# rapidshark-motor-filter-mk-1_0.net
KiCad netlist of a schematic drawn in EAGLE
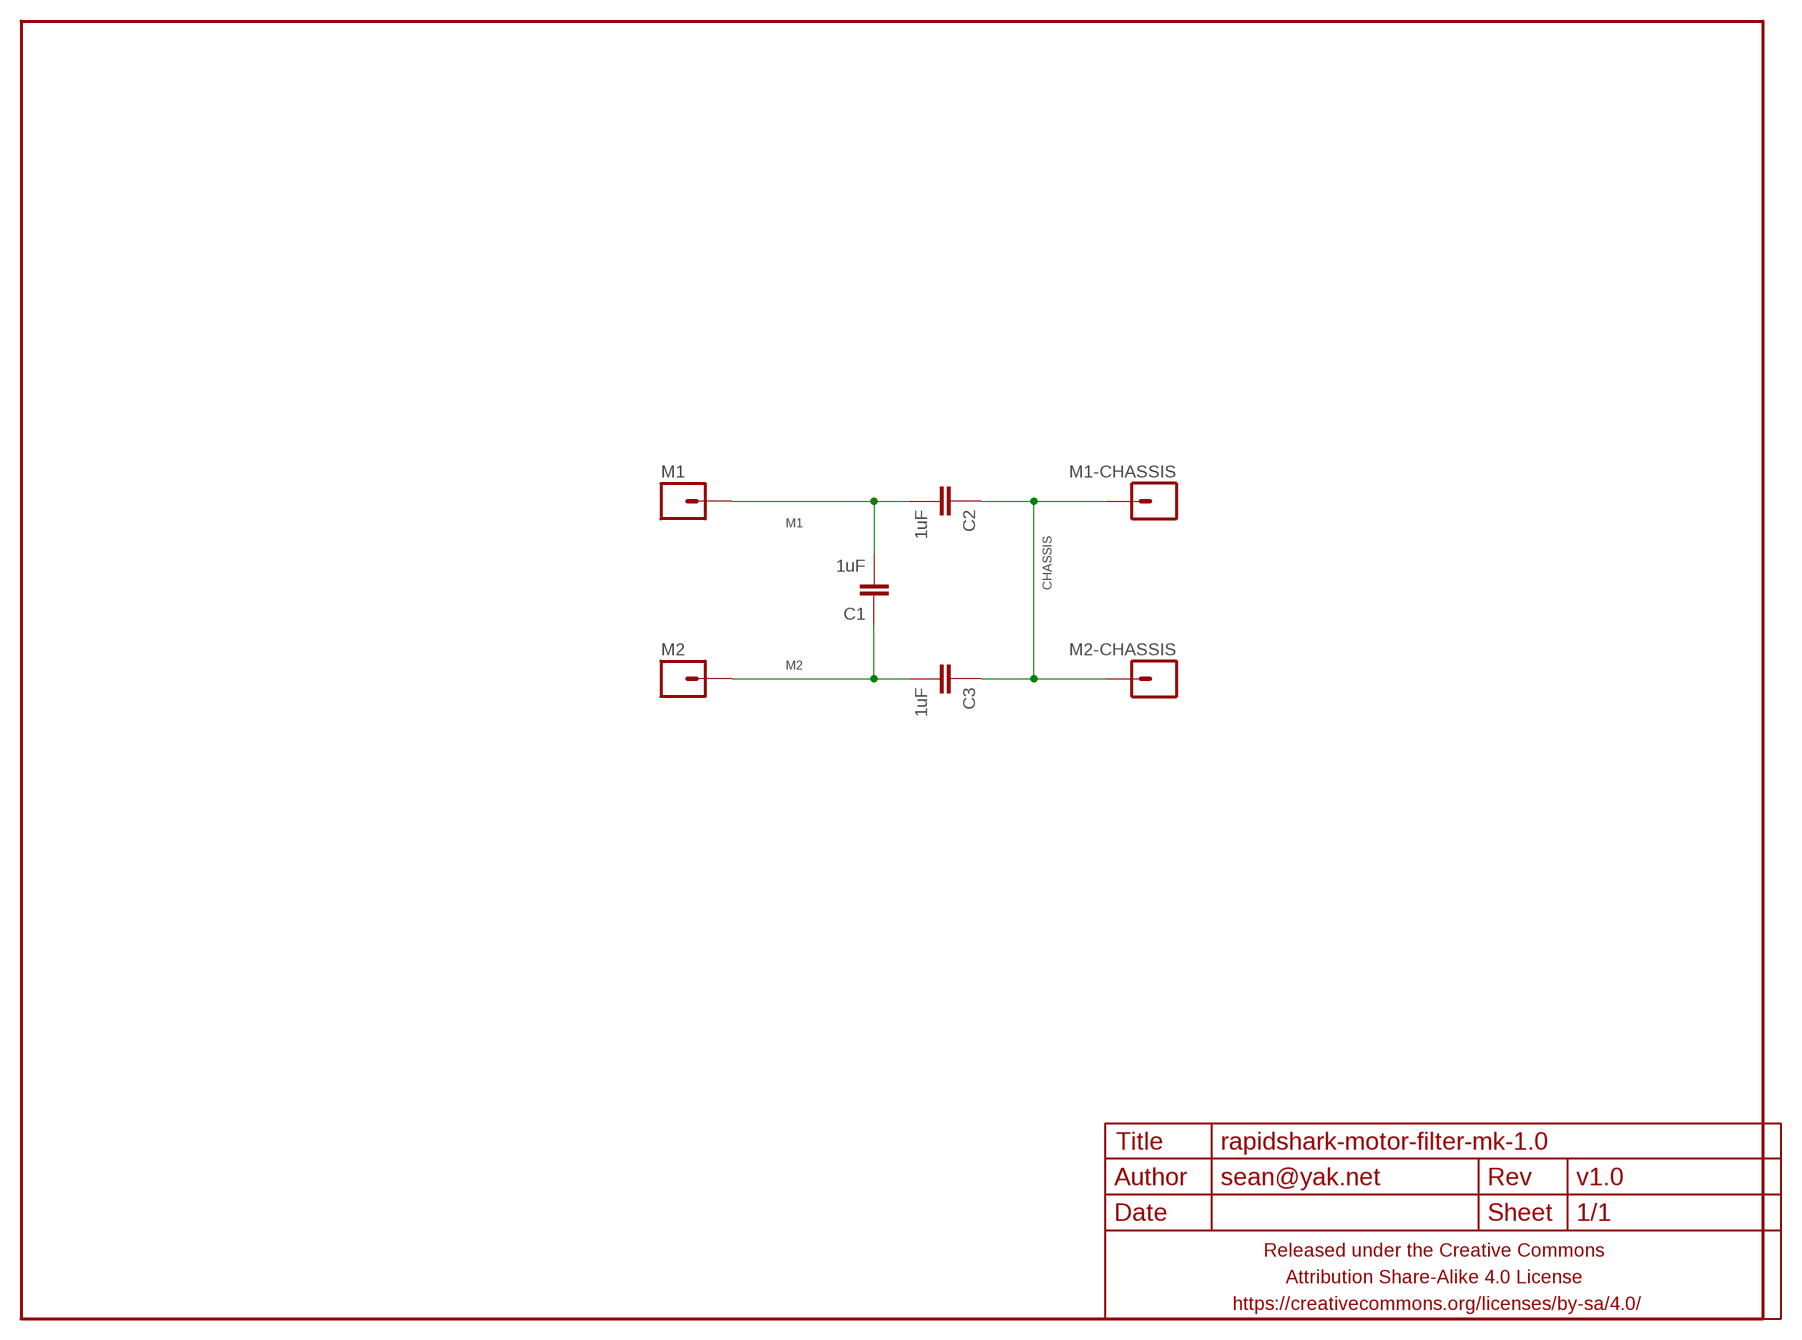
[diagram p0: schematic, sheet 1]

(export (version "E")
  (design (tool "Eeschema 10.0.6"))
  (components
    (comp (ref "C1")
      (value "1uF")
      (footprint "eagle-import:C0805-TIGHTER")
      (libsource (lib "eagle-import") (part "CAPACITOR-CERAMICC0805-TIGHTER"))
    )
    (comp (ref "C2")
      (value "1uF")
      (footprint "eagle-import:C0805-TIGHTER")
      (libsource (lib "eagle-import") (part "CAPACITOR-CERAMICC0805-TIGHTER"))
    )
    (comp (ref "C3")
      (value "1uF")
      (footprint "eagle-import:C0805-TIGHTER")
      (libsource (lib "eagle-import") (part "CAPACITOR-CERAMICC0805-TIGHTER"))
    )
    (comp (ref "FRAME1")
      (value "FRAME-LETTERNO_PACKAGE")
      (footprint "eagle-import:DUMMY")
      (fields (field (name "DESIGNER") "sean@yak.net") (field (name "VERSION") "v1.0"))
      (libsource (lib "eagle-import") (part "FRAME-LETTERNO_PACKAGE"))
    )
    (comp (ref "M1")
      (value "M01PTH-2.5MM")
      (footprint "eagle-import:1X01-2.5MM")
      (libsource (lib "eagle-import") (part "M01PTH-2.5MM"))
    )
    (comp (ref "M1-CHASSIS")
      (value "M01SMDNS")
      (footprint "eagle-import:1X01NS")
      (libsource (lib "eagle-import") (part "M01SMDNS"))
    )
    (comp (ref "M2")
      (value "M01PTH-2.5MM")
      (footprint "eagle-import:1X01-2.5MM")
      (libsource (lib "eagle-import") (part "M01PTH-2.5MM"))
    )
    (comp (ref "M2-CHASSIS")
      (value "M01SMDNS")
      (footprint "eagle-import:1X01NS")
      (libsource (lib "eagle-import") (part "M01SMDNS"))
    )
  )
  (nets
    (net (code "1") (name "/CHASSIS") (class "Default")
      (node (ref "C2") (pin "1") (pinfunction "1_1") (pintype "passive"))
      (node (ref "C3") (pin "1") (pinfunction "1_1") (pintype "passive"))
      (node (ref "M1-CHASSIS") (pin "1") (pinfunction "1_1") (pintype "passive"))
      (node (ref "M2-CHASSIS") (pin "1") (pinfunction "1_1") (pintype "passive"))
    )
    (net (code "2") (name "/M1") (class "Default")
      (node (ref "C1") (pin "2") (pinfunction "2_2") (pintype "passive"))
      (node (ref "C2") (pin "2") (pinfunction "2_2") (pintype "passive"))
      (node (ref "M1") (pin "1") (pinfunction "1_1") (pintype "passive"))
    )
    (net (code "3") (name "/M2") (class "Default")
      (node (ref "C1") (pin "1") (pinfunction "1_1") (pintype "passive"))
      (node (ref "C3") (pin "2") (pinfunction "2_2") (pintype "passive"))
      (node (ref "M2") (pin "1") (pinfunction "1_1") (pintype "passive"))
    )
  )
)
